# schema_v4_4.net
KiCad netlist of a schematic drawn in EAGLE
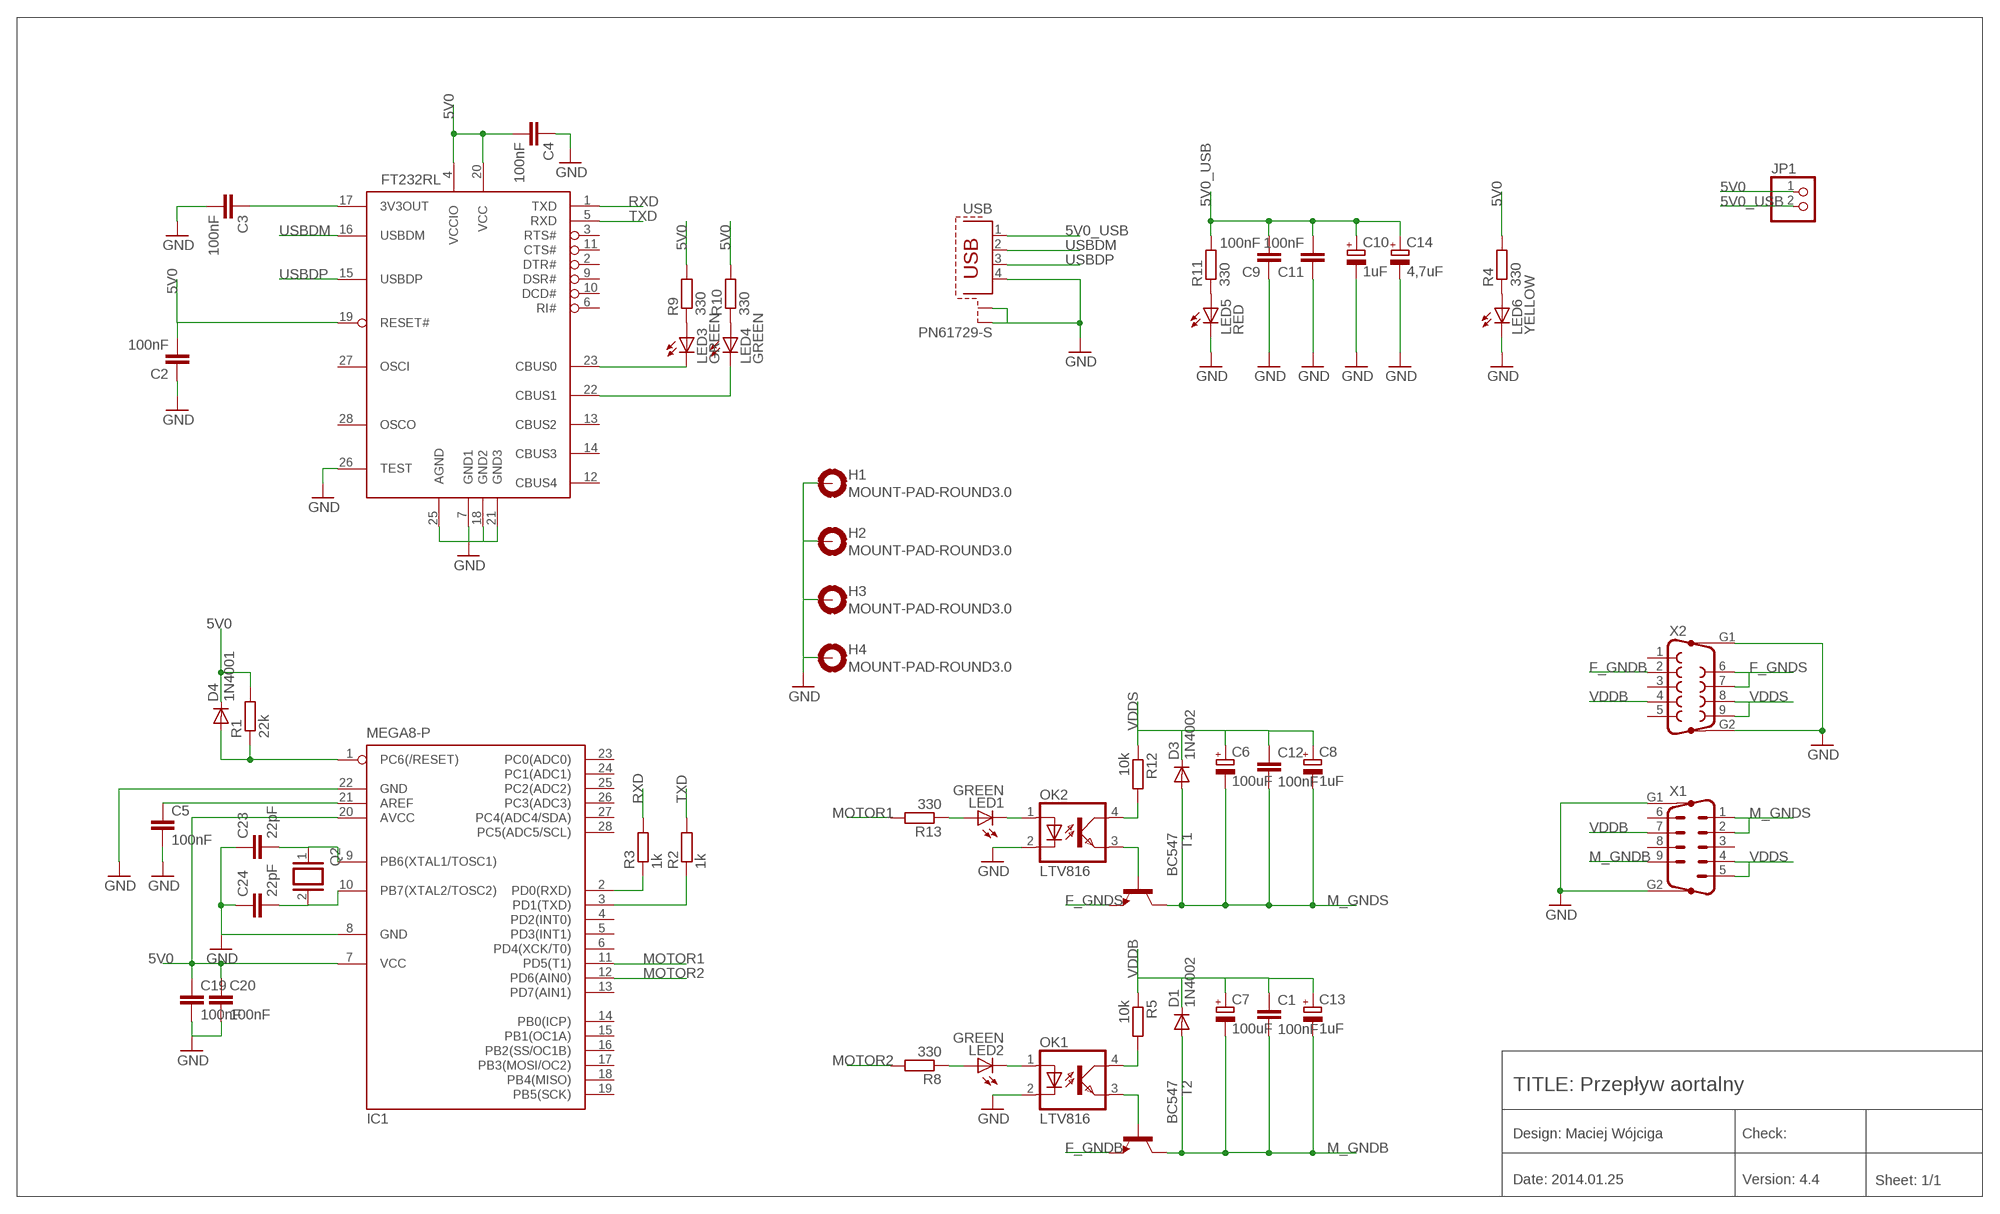
[diagram p0: schematic, sheet 1]

(export (version "E")
  (design (tool "Eeschema 10.0.6"))
  (components
    (comp (ref "C1")
      (value "100nF")
      (footprint "eagle-import:C025-025X050")
      (libsource (lib "eagle-import") (part "C-EU025-025X050"))
    )
    (comp (ref "C2")
      (value "100nF")
      (footprint "eagle-import:C025-025X050")
      (libsource (lib "eagle-import") (part "C-EU025-025X050"))
    )
    (comp (ref "C3")
      (value "100nF")
      (footprint "eagle-import:C025-025X050")
      (libsource (lib "eagle-import") (part "C-EU025-025X050"))
    )
    (comp (ref "C4")
      (value "100nF")
      (footprint "eagle-import:C025-025X050")
      (libsource (lib "eagle-import") (part "C-EU025-025X050"))
    )
    (comp (ref "C5")
      (value "100nF")
      (footprint "eagle-import:C025-025X050")
      (libsource (lib "eagle-import") (part "C-EU025-025X050"))
    )
    (comp (ref "C6")
      (value "100uF")
      (footprint "eagle-import:E5-13")
      (libsource (lib "eagle-import") (part "CPOL-EUE5-13"))
    )
    (comp (ref "C7")
      (value "100uF")
      (footprint "eagle-import:E5-13")
      (libsource (lib "eagle-import") (part "CPOL-EUE5-13"))
    )
    (comp (ref "C8")
      (value "1uF")
      (footprint "eagle-import:E2-4")
      (libsource (lib "eagle-import") (part "CPOL-EUE2-4"))
    )
    (comp (ref "C9")
      (value "100nF")
      (footprint "eagle-import:C025-025X050")
      (libsource (lib "eagle-import") (part "C-EU025-025X050"))
    )
    (comp (ref "C10")
      (value "1uF")
      (footprint "eagle-import:E2,5-5")
      (libsource (lib "eagle-import") (part "CPOL-EUE2.5-5"))
    )
    (comp (ref "C11")
      (value "100nF")
      (footprint "eagle-import:C025-025X050")
      (libsource (lib "eagle-import") (part "C-EU025-025X050"))
    )
    (comp (ref "C12")
      (value "100nF")
      (footprint "eagle-import:C025-025X050")
      (libsource (lib "eagle-import") (part "C-EU025-025X050"))
    )
    (comp (ref "C13")
      (value "1uF")
      (footprint "eagle-import:E2-4")
      (libsource (lib "eagle-import") (part "CPOL-EUE2-4"))
    )
    (comp (ref "C14")
      (value "4,7uF")
      (footprint "eagle-import:E2,5-5")
      (libsource (lib "eagle-import") (part "CPOL-EUE2.5-5"))
    )
    (comp (ref "C19")
      (value "100nF")
      (footprint "eagle-import:C025-025X050")
      (libsource (lib "eagle-import") (part "C-EU025-025X050"))
    )
    (comp (ref "C20")
      (value "100nF")
      (footprint "eagle-import:C025-025X050")
      (libsource (lib "eagle-import") (part "C-EU025-025X050"))
    )
    (comp (ref "C23")
      (value "22pF")
      (footprint "eagle-import:C025-025X050")
      (libsource (lib "eagle-import") (part "C-EU025-025X050"))
    )
    (comp (ref "C24")
      (value "22pF")
      (footprint "eagle-import:C025-025X050")
      (libsource (lib "eagle-import") (part "C-EU025-025X050"))
    )
    (comp (ref "D1")
      (value "1N4002")
      (footprint "eagle-import:DO41-10")
      (libsource (lib "eagle-import") (part "1N4004"))
    )
    (comp (ref "D3")
      (value "1N4002")
      (footprint "eagle-import:DO41-10")
      (libsource (lib "eagle-import") (part "1N4004"))
    )
    (comp (ref "D4")
      (value "1N4001")
      (footprint "eagle-import:DO41-10")
      (libsource (lib "eagle-import") (part "1N4004"))
    )
    (comp (ref "FT232RL")
      (value "FT232RL")
      (footprint "eagle-import:SSOP28DB")
      (libsource (lib "eagle-import") (part "FT232RL"))
    )
    (comp (ref "H1")
      (value "MOUNT-PAD-ROUND3.0")
      (footprint "eagle-import:3,0-PAD")
      (libsource (lib "eagle-import") (part "MOUNT-PAD-ROUND3.0"))
    )
    (comp (ref "H2")
      (value "MOUNT-PAD-ROUND3.0")
      (footprint "eagle-import:3,0-PAD")
      (libsource (lib "eagle-import") (part "MOUNT-PAD-ROUND3.0"))
    )
    (comp (ref "H3")
      (value "MOUNT-PAD-ROUND3.0")
      (footprint "eagle-import:3,0-PAD")
      (libsource (lib "eagle-import") (part "MOUNT-PAD-ROUND3.0"))
    )
    (comp (ref "H4")
      (value "MOUNT-PAD-ROUND3.0")
      (footprint "eagle-import:3,0-PAD")
      (libsource (lib "eagle-import") (part "MOUNT-PAD-ROUND3.0"))
    )
    (comp (ref "IC1")
      (value "MEGA8-P")
      (footprint "eagle-import:DIL28-3")
      (libsource (lib "eagle-import") (part "MEGA8-P"))
    )
    (comp (ref "JP1")
      (value "PINHD-1X2")
      (footprint "eagle-import:1X02")
      (libsource (lib "eagle-import") (part "PINHD-1X2"))
    )
    (comp (ref "LED1")
      (value "GREEN")
      (footprint "eagle-import:LED3MM")
      (libsource (lib "eagle-import") (part "LED3MM"))
    )
    (comp (ref "LED2")
      (value "GREEN")
      (footprint "eagle-import:LED3MM")
      (libsource (lib "eagle-import") (part "LED3MM"))
    )
    (comp (ref "LED3")
      (value "GREEN")
      (footprint "eagle-import:LED3MM")
      (libsource (lib "eagle-import") (part "LED3MM"))
    )
    (comp (ref "LED4")
      (value "GREEN")
      (footprint "eagle-import:LED3MM")
      (libsource (lib "eagle-import") (part "LED3MM"))
    )
    (comp (ref "LED5")
      (value "RED")
      (footprint "eagle-import:LED3MM")
      (libsource (lib "eagle-import") (part "LED3MM"))
    )
    (comp (ref "LED6")
      (value "YELLOW")
      (footprint "eagle-import:LED3MM")
      (libsource (lib "eagle-import") (part "LED3MM"))
    )
    (comp (ref "OK1")
      (value "LTV816")
      (footprint "eagle-import:DIL04")
      (libsource (lib "eagle-import") (part "LTV816"))
    )
    (comp (ref "OK2")
      (value "LTV816")
      (footprint "eagle-import:DIL04")
      (libsource (lib "eagle-import") (part "LTV816"))
    )
    (comp (ref "Q2")
      (value "XTAL/S")
      (footprint "eagle-import:QS")
      (libsource (lib "eagle-import") (part "XTAL/S"))
    )
    (comp (ref "R1")
      (value "22k")
      (footprint "eagle-import:0207_10")
      (libsource (lib "eagle-import") (part "R-EU_0207/10"))
    )
    (comp (ref "R2")
      (value "1k")
      (footprint "eagle-import:0207_10")
      (libsource (lib "eagle-import") (part "R-EU_0207/10"))
    )
    (comp (ref "R3")
      (value "1k")
      (footprint "eagle-import:0207_10")
      (libsource (lib "eagle-import") (part "R-EU_0207/10"))
    )
    (comp (ref "R4")
      (value "330")
      (footprint "eagle-import:0207_10")
      (libsource (lib "eagle-import") (part "R-EU_0207/10"))
    )
    (comp (ref "R5")
      (value "10k")
      (footprint "eagle-import:0207_10")
      (libsource (lib "eagle-import") (part "R-EU_0207/10"))
    )
    (comp (ref "R8")
      (value "330")
      (footprint "eagle-import:0207_10")
      (libsource (lib "eagle-import") (part "R-EU_0207/10"))
    )
    (comp (ref "R9")
      (value "330")
      (footprint "eagle-import:0207_10")
      (libsource (lib "eagle-import") (part "R-EU_0207/10"))
    )
    (comp (ref "R10")
      (value "330")
      (footprint "eagle-import:0207_10")
      (libsource (lib "eagle-import") (part "R-EU_0207/10"))
    )
    (comp (ref "R11")
      (value "330")
      (footprint "eagle-import:0207_10")
      (libsource (lib "eagle-import") (part "R-EU_0207/10"))
    )
    (comp (ref "R12")
      (value "10k")
      (footprint "eagle-import:0207_10")
      (libsource (lib "eagle-import") (part "R-EU_0207/10"))
    )
    (comp (ref "R13")
      (value "330")
      (footprint "eagle-import:0207_10")
      (libsource (lib "eagle-import") (part "R-EU_0207/10"))
    )
    (comp (ref "T1")
      (value "BC547")
      (footprint "eagle-import:TO92")
      (libsource (lib "eagle-import") (part "BC547"))
    )
    (comp (ref "T2")
      (value "BC547")
      (footprint "eagle-import:TO92")
      (libsource (lib "eagle-import") (part "BC547"))
    )
    (comp (ref "USB")
      (value "PN61729-S")
      (footprint "eagle-import:PN61729-S")
      (fields (field (name "OC_FARNELL") "unknown") (field (name "OC_NEWARK") "unknown"))
      (libsource (lib "eagle-import") (part "PN61729-S"))
    )
    (comp (ref "X1")
      (value "M09HP")
      (footprint "eagle-import:M09HP")
      (libsource (lib "eagle-import") (part "M09HP"))
    )
    (comp (ref "X2")
      (value "F09HP")
      (footprint "eagle-import:F09HP")
      (libsource (lib "eagle-import") (part "F09HP"))
    )
  )
  (nets
    (net (code "1") (name "/5V0") (class "Default")
      (node (ref "C19") (pin "1") (pinfunction "1_1") (pintype "passive"))
      (node (ref "C2") (pin "2") (pinfunction "2_2") (pintype "passive"))
      (node (ref "C20") (pin "1") (pinfunction "1_1") (pintype "passive"))
      (node (ref "C4") (pin "2") (pinfunction "2_2") (pintype "passive"))
      (node (ref "D4") (pin "C") (pinfunction "C_C") (pintype "passive"))
      (node (ref "FT232RL") (pin "19") (pinfunction "RESET#_19") (pintype "input"))
      (node (ref "FT232RL") (pin "20") (pinfunction "VCC_20") (pintype "power_in"))
      (node (ref "FT232RL") (pin "4") (pinfunction "VCCIO_4") (pintype "power_in"))
      (node (ref "IC1") (pin "20") (pinfunction "AVCC_20") (pintype "power_in"))
      (node (ref "IC1") (pin "7") (pinfunction "VCC_7") (pintype "power_in"))
      (node (ref "JP1") (pin "1") (pinfunction "1_1") (pintype "passive"))
      (node (ref "R1") (pin "2") (pinfunction "2_2") (pintype "passive"))
      (node (ref "R10") (pin "2") (pinfunction "2_2") (pintype "passive"))
      (node (ref "R4") (pin "2") (pinfunction "2_2") (pintype "passive"))
      (node (ref "R9") (pin "2") (pinfunction "2_2") (pintype "passive"))
    )
    (net (code "2") (name "/5V0_USB") (class "Default")
      (node (ref "C10") (pin "+") (pinfunction "+_+") (pintype "passive"))
      (node (ref "C11") (pin "2") (pinfunction "2_2") (pintype "passive"))
      (node (ref "C14") (pin "+") (pinfunction "+_+") (pintype "passive"))
      (node (ref "C9") (pin "2") (pinfunction "2_2") (pintype "passive"))
      (node (ref "JP1") (pin "2") (pinfunction "2_2") (pintype "passive"))
      (node (ref "R11") (pin "2") (pinfunction "2_2") (pintype "passive"))
      (node (ref "USB") (pin "1") (pinfunction "1_1") (pintype "passive"))
    )
    (net (code "3") (name "/F_GNDB") (class "Default")
      (node (ref "T2") (pin "1") (pinfunction "E_1") (pintype "passive"))
      (node (ref "X2") (pin "2") (pinfunction "2_2") (pintype "passive"))
    )
    (net (code "4") (name "/F_GNDS") (class "Default")
      (node (ref "T1") (pin "1") (pinfunction "E_1") (pintype "passive"))
      (node (ref "X2") (pin "6") (pinfunction "6_6") (pintype "passive"))
      (node (ref "X2") (pin "7") (pinfunction "7_7") (pintype "passive"))
    )
    (net (code "5") (name "/MOTOR1") (class "Default")
      (node (ref "IC1") (pin "11") (pinfunction "PD5(T1)_11") (pintype "bidirectional"))
      (node (ref "R13") (pin "2") (pinfunction "2_2") (pintype "passive"))
    )
    (net (code "6") (name "/MOTOR2") (class "Default")
      (node (ref "IC1") (pin "12") (pinfunction "PD6(AIN0)_12") (pintype "bidirectional"))
      (node (ref "R8") (pin "2") (pinfunction "2_2") (pintype "passive"))
    )
    (net (code "7") (name "/M_GNDB") (class "Default")
      (node (ref "C1") (pin "2") (pinfunction "2_2") (pintype "passive"))
      (node (ref "C13") (pin "-") (pinfunction "-_-") (pintype "passive"))
      (node (ref "C7") (pin "-") (pinfunction "-_-") (pintype "passive"))
      (node (ref "D1") (pin "A") (pinfunction "A_A") (pintype "passive"))
      (node (ref "T2") (pin "3") (pinfunction "C_3") (pintype "passive"))
      (node (ref "X1") (pin "9") (pinfunction "9_9") (pintype "passive"))
    )
    (net (code "8") (name "/M_GNDS") (class "Default")
      (node (ref "C12") (pin "2") (pinfunction "2_2") (pintype "passive"))
      (node (ref "C6") (pin "-") (pinfunction "-_-") (pintype "passive"))
      (node (ref "C8") (pin "-") (pinfunction "-_-") (pintype "passive"))
      (node (ref "D3") (pin "A") (pinfunction "A_A") (pintype "passive"))
      (node (ref "T1") (pin "3") (pinfunction "C_3") (pintype "passive"))
      (node (ref "X1") (pin "1") (pinfunction "1_1") (pintype "passive"))
      (node (ref "X1") (pin "2") (pinfunction "2_2") (pintype "passive"))
    )
    (net (code "9") (name "/RXD") (class "Default")
      (node (ref "FT232RL") (pin "1") (pinfunction "TXD_1") (pintype "output"))
      (node (ref "R3") (pin "2") (pinfunction "2_2") (pintype "passive"))
    )
    (net (code "10") (name "/TXD") (class "Default")
      (node (ref "FT232RL") (pin "5") (pinfunction "RXD_5") (pintype "input"))
      (node (ref "R2") (pin "2") (pinfunction "2_2") (pintype "passive"))
    )
    (net (code "11") (name "/USBDM") (class "Default")
      (node (ref "FT232RL") (pin "16") (pinfunction "USBDM_16") (pintype "bidirectional"))
      (node (ref "USB") (pin "2") (pinfunction "2_2") (pintype "passive"))
    )
    (net (code "12") (name "/USBDP") (class "Default")
      (node (ref "FT232RL") (pin "15") (pinfunction "USBDP_15") (pintype "bidirectional"))
      (node (ref "USB") (pin "3") (pinfunction "3_3") (pintype "passive"))
    )
    (net (code "13") (name "/VDDB") (class "Default")
      (node (ref "C1") (pin "1") (pinfunction "1_1") (pintype "passive"))
      (node (ref "C13") (pin "+") (pinfunction "+_+") (pintype "passive"))
      (node (ref "C7") (pin "+") (pinfunction "+_+") (pintype "passive"))
      (node (ref "D1") (pin "C") (pinfunction "C_C") (pintype "passive"))
      (node (ref "R5") (pin "1") (pinfunction "1_1") (pintype "passive"))
      (node (ref "X1") (pin "7") (pinfunction "7_7") (pintype "passive"))
      (node (ref "X2") (pin "4") (pinfunction "4_4") (pintype "passive"))
    )
    (net (code "14") (name "/VDDS") (class "Default")
      (node (ref "C12") (pin "1") (pinfunction "1_1") (pintype "passive"))
      (node (ref "C6") (pin "+") (pinfunction "+_+") (pintype "passive"))
      (node (ref "C8") (pin "+") (pinfunction "+_+") (pintype "passive"))
      (node (ref "D3") (pin "C") (pinfunction "C_C") (pintype "passive"))
      (node (ref "R12") (pin "1") (pinfunction "1_1") (pintype "passive"))
      (node (ref "X1") (pin "4") (pinfunction "4_4") (pintype "passive"))
      (node (ref "X1") (pin "5") (pinfunction "5_5") (pintype "passive"))
      (node (ref "X2") (pin "8") (pinfunction "8_8") (pintype "passive"))
      (node (ref "X2") (pin "9") (pinfunction "9_9") (pintype "passive"))
    )
    (net (code "15") (name "GND") (class "Default")
      (node (ref "C10") (pin "-") (pinfunction "-_-") (pintype "passive"))
      (node (ref "C11") (pin "1") (pinfunction "1_1") (pintype "passive"))
      (node (ref "C14") (pin "-") (pinfunction "-_-") (pintype "passive"))
      (node (ref "C19") (pin "2") (pinfunction "2_2") (pintype "passive"))
      (node (ref "C2") (pin "1") (pinfunction "1_1") (pintype "passive"))
      (node (ref "C20") (pin "2") (pinfunction "2_2") (pintype "passive"))
      (node (ref "C23") (pin "1") (pinfunction "1_1") (pintype "passive"))
      (node (ref "C24") (pin "1") (pinfunction "1_1") (pintype "passive"))
      (node (ref "C3") (pin "2") (pinfunction "2_2") (pintype "passive"))
      (node (ref "C4") (pin "1") (pinfunction "1_1") (pintype "passive"))
      (node (ref "C5") (pin "2") (pinfunction "2_2") (pintype "passive"))
      (node (ref "C9") (pin "1") (pinfunction "1_1") (pintype "passive"))
      (node (ref "FT232RL") (pin "18") (pinfunction "GND2_18") (pintype "power_in"))
      (node (ref "FT232RL") (pin "21") (pinfunction "GND3_21") (pintype "power_in"))
      (node (ref "FT232RL") (pin "25") (pinfunction "AGND_25") (pintype "power_in"))
      (node (ref "FT232RL") (pin "26") (pinfunction "TEST_26") (pintype "input"))
      (node (ref "FT232RL") (pin "7") (pinfunction "GND1_7") (pintype "power_in"))
      (node (ref "H1") (pin "B3,0") (pinfunction "MOUNT_B3,0") (pintype "passive"))
      (node (ref "H2") (pin "B3,0") (pinfunction "MOUNT_B3,0") (pintype "passive"))
      (node (ref "H3") (pin "B3,0") (pinfunction "MOUNT_B3,0") (pintype "passive"))
      (node (ref "H4") (pin "B3,0") (pinfunction "MOUNT_B3,0") (pintype "passive"))
      (node (ref "IC1") (pin "22") (pinfunction "GND_22") (pintype "power_in"))
      (node (ref "IC1") (pin "8") (pinfunction "GND_8") (pintype "power_in"))
      (node (ref "LED5") (pin "K") (pinfunction "C_K") (pintype "passive"))
      (node (ref "LED6") (pin "K") (pinfunction "C_K") (pintype "passive"))
      (node (ref "OK1") (pin "2") (pinfunction "C_2") (pintype "passive"))
      (node (ref "OK2") (pin "2") (pinfunction "C_2") (pintype "passive"))
      (node (ref "USB") (pin "4") (pinfunction "4_4") (pintype "passive"))
      (node (ref "USB") (pin "S1") (pinfunction "S1_S1") (pintype "passive"))
      (node (ref "USB") (pin "S2") (pinfunction "S2_S2") (pintype "passive"))
      (node (ref "X1") (pin "G1") (pinfunction "G1_G1") (pintype "passive"))
      (node (ref "X1") (pin "G2") (pinfunction "G2_G2") (pintype "passive"))
      (node (ref "X2") (pin "G1") (pinfunction "G1_G1") (pintype "passive"))
      (node (ref "X2") (pin "G2") (pinfunction "G2_G2") (pintype "passive"))
    )
    (net (code "16") (name "Net-(FT232RL-3V3OUT)") (class "Default")
      (node (ref "C3") (pin "1") (pinfunction "1_1") (pintype "passive"))
      (node (ref "FT232RL") (pin "17") (pinfunction "3V3OUT_17") (pintype "output"))
    )
    (net (code "17") (name "Net-(FT232RL-CBUS0)") (class "Default")
      (node (ref "FT232RL") (pin "23") (pinfunction "CBUS0_23") (pintype "bidirectional"))
      (node (ref "LED3") (pin "K") (pinfunction "C_K") (pintype "passive"))
    )
    (net (code "18") (name "Net-(FT232RL-CBUS1)") (class "Default")
      (node (ref "FT232RL") (pin "22") (pinfunction "CBUS1_22") (pintype "bidirectional"))
      (node (ref "LED4") (pin "K") (pinfunction "C_K") (pintype "passive"))
    )
    (net (code "19") (name "Net-(IC1-AREF)") (class "Default")
      (node (ref "C5") (pin "1") (pinfunction "1_1") (pintype "passive"))
      (node (ref "IC1") (pin "21") (pinfunction "AREF_21") (pintype "passive"))
    )
    (net (code "20") (name "Net-(IC1-PB6(XTAL1{slash}TOSC1))") (class "Default")
      (node (ref "C23") (pin "2") (pinfunction "2_2") (pintype "passive"))
      (node (ref "IC1") (pin "9") (pinfunction "PB6(XTAL1/TOSC1)_9") (pintype "bidirectional"))
      (node (ref "Q2") (pin "1") (pinfunction "1_1") (pintype "passive"))
    )
    (net (code "21") (name "Net-(IC1-PB7(XTAL2{slash}TOSC2))") (class "Default")
      (node (ref "C24") (pin "2") (pinfunction "2_2") (pintype "passive"))
      (node (ref "IC1") (pin "10") (pinfunction "PB7(XTAL2/TOSC2)_10") (pintype "bidirectional"))
      (node (ref "Q2") (pin "2") (pinfunction "2_2") (pintype "passive"))
    )
    (net (code "22") (name "Net-(IC1-PC6({slash}RESET))") (class "Default")
      (node (ref "D4") (pin "A") (pinfunction "A_A") (pintype "passive"))
      (node (ref "IC1") (pin "1") (pinfunction "PC6(/RESET)_1") (pintype "bidirectional"))
      (node (ref "R1") (pin "1") (pinfunction "1_1") (pintype "passive"))
    )
    (net (code "23") (name "Net-(IC1-PD0(RXD))") (class "Default")
      (node (ref "IC1") (pin "2") (pinfunction "PD0(RXD)_2") (pintype "bidirectional"))
      (node (ref "R3") (pin "1") (pinfunction "1_1") (pintype "passive"))
    )
    (net (code "24") (name "Net-(IC1-PD1(TXD))") (class "Default")
      (node (ref "IC1") (pin "3") (pinfunction "PD1(TXD)_3") (pintype "bidirectional"))
      (node (ref "R2") (pin "1") (pinfunction "1_1") (pintype "passive"))
    )
    (net (code "25") (name "Net-(LED1-C)") (class "Default")
      (node (ref "LED1") (pin "K") (pinfunction "C_K") (pintype "passive"))
      (node (ref "OK2") (pin "1") (pinfunction "A_1") (pintype "passive"))
    )
    (net (code "26") (name "Net-(LED1-PadA)") (class "Default")
      (node (ref "LED1") (pin "A") (pinfunction "A_A") (pintype "passive"))
      (node (ref "R13") (pin "1") (pinfunction "1_1") (pintype "passive"))
    )
    (net (code "27") (name "Net-(LED2-C)") (class "Default")
      (node (ref "LED2") (pin "K") (pinfunction "C_K") (pintype "passive"))
      (node (ref "OK1") (pin "1") (pinfunction "A_1") (pintype "passive"))
    )
    (net (code "28") (name "Net-(LED2-PadA)") (class "Default")
      (node (ref "LED2") (pin "A") (pinfunction "A_A") (pintype "passive"))
      (node (ref "R8") (pin "1") (pinfunction "1_1") (pintype "passive"))
    )
    (net (code "29") (name "Net-(LED3-PadA)") (class "Default")
      (node (ref "LED3") (pin "A") (pinfunction "A_A") (pintype "passive"))
      (node (ref "R9") (pin "1") (pinfunction "1_1") (pintype "passive"))
    )
    (net (code "30") (name "Net-(LED4-PadA)") (class "Default")
      (node (ref "LED4") (pin "A") (pinfunction "A_A") (pintype "passive"))
      (node (ref "R10") (pin "1") (pinfunction "1_1") (pintype "passive"))
    )
    (net (code "31") (name "Net-(LED5-PadA)") (class "Default")
      (node (ref "LED5") (pin "A") (pinfunction "A_A") (pintype "passive"))
      (node (ref "R11") (pin "1") (pinfunction "1_1") (pintype "passive"))
    )
    (net (code "32") (name "Net-(LED6-PadA)") (class "Default")
      (node (ref "LED6") (pin "A") (pinfunction "A_A") (pintype "passive"))
      (node (ref "R4") (pin "1") (pinfunction "1_1") (pintype "passive"))
    )
    (net (code "33") (name "Net-(OK1-COL)") (class "Default")
      (node (ref "OK1") (pin "4") (pinfunction "COL_4") (pintype "passive"))
      (node (ref "R5") (pin "2") (pinfunction "2_2") (pintype "passive"))
    )
    (net (code "34") (name "Net-(OK1-EMIT)") (class "Default")
      (node (ref "OK1") (pin "3") (pinfunction "EMIT_3") (pintype "passive"))
      (node (ref "T2") (pin "2") (pinfunction "B_2") (pintype "passive"))
    )
    (net (code "35") (name "Net-(OK2-COL)") (class "Default")
      (node (ref "OK2") (pin "4") (pinfunction "COL_4") (pintype "passive"))
      (node (ref "R12") (pin "2") (pinfunction "2_2") (pintype "passive"))
    )
    (net (code "36") (name "Net-(OK2-EMIT)") (class "Default")
      (node (ref "OK2") (pin "3") (pinfunction "EMIT_3") (pintype "passive"))
      (node (ref "T1") (pin "2") (pinfunction "B_2") (pintype "passive"))
    )
    (net (code "37") (name "unconnected-(FT232RL-CBUS2-Pad13)") (class "Default")
      (node (ref "FT232RL") (pin "13") (pinfunction "CBUS2_13") (pintype "bidirectional"))
    )
    (net (code "38") (name "unconnected-(FT232RL-CBUS3-Pad14)") (class "Default")
      (node (ref "FT232RL") (pin "14") (pinfunction "CBUS3_14") (pintype "bidirectional"))
    )
    (net (code "39") (name "unconnected-(FT232RL-CBUS4-Pad12)") (class "Default")
      (node (ref "FT232RL") (pin "12") (pinfunction "CBUS4_12") (pintype "bidirectional"))
    )
    (net (code "40") (name "unconnected-(FT232RL-CTS#-Pad11)") (class "Default")
      (node (ref "FT232RL") (pin "11") (pinfunction "CTS#_11") (pintype "input"))
    )
    (net (code "41") (name "unconnected-(FT232RL-DCD#-Pad10)") (class "Default")
      (node (ref "FT232RL") (pin "10") (pinfunction "DCD#_10") (pintype "input"))
    )
    (net (code "42") (name "unconnected-(FT232RL-DSR#-Pad9)") (class "Default")
      (node (ref "FT232RL") (pin "9") (pinfunction "DSR#_9") (pintype "input"))
    )
    (net (code "43") (name "unconnected-(FT232RL-DTR#-Pad2)") (class "Default")
      (node (ref "FT232RL") (pin "2") (pinfunction "DTR#_2") (pintype "output"))
    )
    (net (code "44") (name "unconnected-(FT232RL-OSCI-Pad27)") (class "Default")
      (node (ref "FT232RL") (pin "27") (pinfunction "OSCI_27") (pintype "input"))
    )
    (net (code "45") (name "unconnected-(FT232RL-OSCO-Pad28)") (class "Default")
      (node (ref "FT232RL") (pin "28") (pinfunction "OSCO_28") (pintype "output"))
    )
    (net (code "46") (name "unconnected-(FT232RL-RI#-Pad6)") (class "Default")
      (node (ref "FT232RL") (pin "6") (pinfunction "RI#_6") (pintype "input"))
    )
    (net (code "47") (name "unconnected-(FT232RL-RTS#-Pad3)") (class "Default")
      (node (ref "FT232RL") (pin "3") (pinfunction "RTS#_3") (pintype "output"))
    )
    (net (code "48") (name "unconnected-(IC1-PB0(ICP)-Pad14)") (class "Default")
      (node (ref "IC1") (pin "14") (pinfunction "PB0(ICP)_14") (pintype "bidirectional"))
    )
    (net (code "49") (name "unconnected-(IC1-PB1(OC1A)-Pad15)") (class "Default")
      (node (ref "IC1") (pin "15") (pinfunction "PB1(OC1A)_15") (pintype "bidirectional"))
    )
    (net (code "50") (name "unconnected-(IC1-PB2(SS{slash}OC1B)-Pad16)") (class "Default")
      (node (ref "IC1") (pin "16") (pinfunction "PB2(SS/OC1B)_16") (pintype "bidirectional"))
    )
    (net (code "51") (name "unconnected-(IC1-PB3(MOSI{slash}OC2)-Pad17)") (class "Default")
      (node (ref "IC1") (pin "17") (pinfunction "PB3(MOSI/OC2)_17") (pintype "bidirectional"))
    )
    (net (code "52") (name "unconnected-(IC1-PB4(MISO)-Pad18)") (class "Default")
      (node (ref "IC1") (pin "18") (pinfunction "PB4(MISO)_18") (pintype "bidirectional"))
    )
    (net (code "53") (name "unconnected-(IC1-PB5(SCK)-Pad19)") (class "Default")
      (node (ref "IC1") (pin "19") (pinfunction "PB5(SCK)_19") (pintype "bidirectional"))
    )
    (net (code "54") (name "unconnected-(IC1-PC0(ADC0)-Pad23)") (class "Default")
      (node (ref "IC1") (pin "23") (pinfunction "PC0(ADC0)_23") (pintype "bidirectional"))
    )
    (net (code "55") (name "unconnected-(IC1-PC1(ADC1)-Pad24)") (class "Default")
      (node (ref "IC1") (pin "24") (pinfunction "PC1(ADC1)_24") (pintype "bidirectional"))
    )
    (net (code "56") (name "unconnected-(IC1-PC2(ADC2)-Pad25)") (class "Default")
      (node (ref "IC1") (pin "25") (pinfunction "PC2(ADC2)_25") (pintype "bidirectional"))
    )
    (net (code "57") (name "unconnected-(IC1-PC3(ADC3)-Pad26)") (class "Default")
      (node (ref "IC1") (pin "26") (pinfunction "PC3(ADC3)_26") (pintype "bidirectional"))
    )
    (net (code "58") (name "unconnected-(IC1-PC4(ADC4{slash}SDA)-Pad27)") (class "Default")
      (node (ref "IC1") (pin "27") (pinfunction "PC4(ADC4/SDA)_27") (pintype "bidirectional"))
    )
    (net (code "59") (name "unconnected-(IC1-PC5(ADC5{slash}SCL)-Pad28)") (class "Default")
      (node (ref "IC1") (pin "28") (pinfunction "PC5(ADC5/SCL)_28") (pintype "bidirectional"))
    )
    (net (code "60") (name "unconnected-(IC1-PD2(INT0)-Pad4)") (class "Default")
      (node (ref "IC1") (pin "4") (pinfunction "PD2(INT0)_4") (pintype "bidirectional"))
    )
    (net (code "61") (name "unconnected-(IC1-PD3(INT1)-Pad5)") (class "Default")
      (node (ref "IC1") (pin "5") (pinfunction "PD3(INT1)_5") (pintype "bidirectional"))
    )
    (net (code "62") (name "unconnected-(IC1-PD4(XCK{slash}T0)-Pad6)") (class "Default")
      (node (ref "IC1") (pin "6") (pinfunction "PD4(XCK/T0)_6") (pintype "bidirectional"))
    )
    (net (code "63") (name "unconnected-(IC1-PD7(AIN1)-Pad13)") (class "Default")
      (node (ref "IC1") (pin "13") (pinfunction "PD7(AIN1)_13") (pintype "bidirectional"))
    )
    (net (code "64") (name "unconnected-(X1-Pad3)") (class "Default")
      (node (ref "X1") (pin "3") (pinfunction "3_3") (pintype "passive"))
    )
    (net (code "65") (name "unconnected-(X1-Pad6)") (class "Default")
      (node (ref "X1") (pin "6") (pinfunction "6_6") (pintype "passive"))
    )
    (net (code "66") (name "unconnected-(X1-Pad8)") (class "Default")
      (node (ref "X1") (pin "8") (pinfunction "8_8") (pintype "passive"))
    )
    (net (code "67") (name "unconnected-(X2-Pad1)") (class "Default")
      (node (ref "X2") (pin "1") (pinfunction "1_1") (pintype "passive"))
    )
    (net (code "68") (name "unconnected-(X2-Pad3)") (class "Default")
      (node (ref "X2") (pin "3") (pinfunction "3_3") (pintype "passive"))
    )
    (net (code "69") (name "unconnected-(X2-Pad5)") (class "Default")
      (node (ref "X2") (pin "5") (pinfunction "5_5") (pintype "passive"))
    )
  )
)
